# adalogger_featherwing.net
KiCad netlist of a schematic drawn in EAGLE
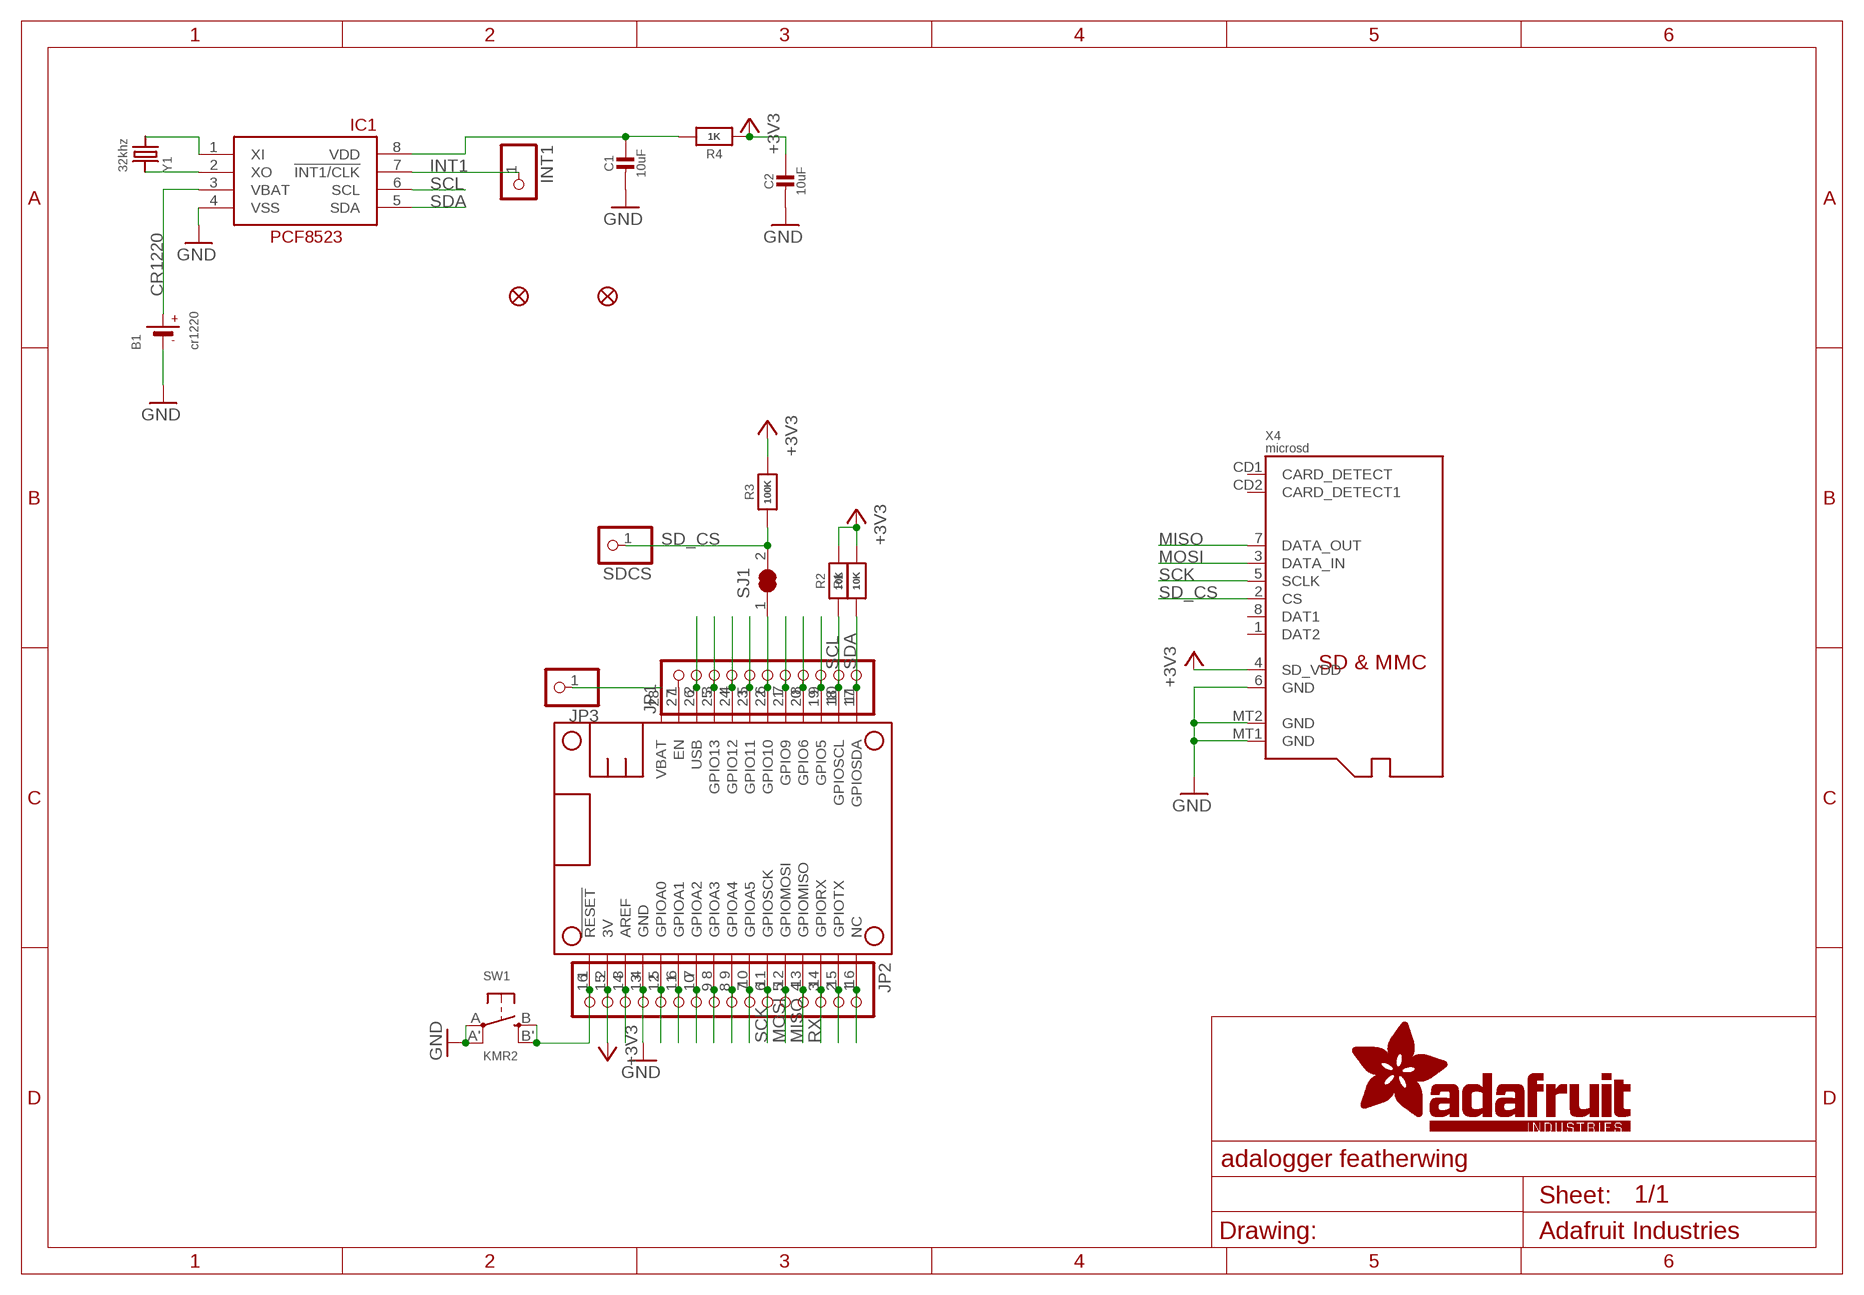
[diagram p0: schematic, sheet 1]

(export (version "E")
  (design (tool "Eeschema 10.0.6"))
  (components
    (comp (ref "B1")
      (value "cr1220")
      (footprint "eagle-import:CR1220-2")
      (libsource (lib "eagle-import") (part "BATTERYCR1220_2"))
    )
    (comp (ref "C1")
      (value "10uF")
      (footprint "eagle-import:0805-NO")
      (libsource (lib "eagle-import") (part "CAP_CERAMIC0805-NOOUTLINE"))
    )
    (comp (ref "C2")
      (value "10uF")
      (footprint "eagle-import:0805-NO")
      (libsource (lib "eagle-import") (part "CAP_CERAMIC0805-NOOUTLINE"))
    )
    (comp (ref "FID1")
      (value "FIDUCIAL_1MM")
      (footprint "eagle-import:FIDUCIAL_1MM")
      (libsource (lib "eagle-import") (part "FIDUCIAL_1MM"))
    )
    (comp (ref "FID2")
      (value "FIDUCIAL_1MM")
      (footprint "eagle-import:FIDUCIAL_1MM")
      (libsource (lib "eagle-import") (part "FIDUCIAL_1MM"))
    )
    (comp (ref "IC1")
      (value "PCF8523T")
      (footprint "eagle-import:SOIC8_150MIL")
      (libsource (lib "eagle-import") (part "RTC_PCF8523T"))
    )
    (comp (ref "INT1")
      (value "HEADER-1X1ROUND")
      (footprint "eagle-import:1X01_ROUND")
      (libsource (lib "eagle-import") (part "HEADER-1X1ROUND"))
    )
    (comp (ref "JP1")
      (value "HEADER-1X11")
      (footprint "eagle-import:1X11_ROUND")
      (libsource (lib "eagle-import") (part "HEADER-1X11"))
    )
    (comp (ref "JP2")
      (value "HEADER-1X16ROUND")
      (footprint "eagle-import:1X16_ROUND")
      (libsource (lib "eagle-import") (part "HEADER-1X16ROUND"))
    )
    (comp (ref "JP3")
      (value "HEADER-1X1ROUND")
      (footprint "eagle-import:1X01_ROUND")
      (libsource (lib "eagle-import") (part "HEADER-1X1ROUND"))
    )
    (comp (ref "MS1")
      (value "FEATHERWING_NODIM")
      (footprint "eagle-import:FEATHERWING_NODIM")
      (libsource (lib "eagle-import") (part "FEATHERWING_NODIM"))
    )
    (comp (ref "R1")
      (value "10K")
      (footprint "eagle-import:0603-NO")
      (libsource (lib "eagle-import") (part "RESISTOR_0603_NOOUT"))
    )
    (comp (ref "R2")
      (value "10K")
      (footprint "eagle-import:0603-NO")
      (libsource (lib "eagle-import") (part "RESISTOR_0603_NOOUT"))
    )
    (comp (ref "R3")
      (value "100K")
      (footprint "eagle-import:0603-NO")
      (libsource (lib "eagle-import") (part "RESISTOR_0603_NOOUT"))
    )
    (comp (ref "R4")
      (value "1K")
      (footprint "eagle-import:0603-NO")
      (libsource (lib "eagle-import") (part "RESISTOR_0603_NOOUT"))
    )
    (comp (ref "SDCS")
      (value "HEADER-1X1ROUND")
      (footprint "eagle-import:1X01_ROUND")
      (libsource (lib "eagle-import") (part "HEADER-1X1ROUND"))
    )
    (comp (ref "SJ1")
      (value "SOLDERJUMPER_CLOSED")
      (footprint "eagle-import:SOLDERJUMPER_CLOSEDWIRE")
      (libsource (lib "eagle-import") (part "SOLDERJUMPER_CLOSED"))
    )
    (comp (ref "SW1")
      (value "KMR2")
      (footprint "eagle-import:BTN_KMR2_4.6X2.8")
      (libsource (lib "eagle-import") (part "SWITCH_TACT_SMT4.6X2.8"))
    )
    (comp (ref "X4")
      (value "microsd")
      (footprint "eagle-import:MICROSD")
      (libsource (lib "eagle-import") (part "MICROSD"))
    )
    (comp (ref "Y1")
      (value "32khz")
      (footprint "eagle-import:CRYSTAL_8X3.8")
      (libsource (lib "eagle-import") (part "CRYSTAL8.0X3.8"))
    )
  )
  (nets
    (net (code "1") (name "+3V3") (class "Default")
      (node (ref "C2") (pin "1") (pinfunction "1_1") (pintype "passive"))
      (node (ref "JP2") (pin "15") (pinfunction "15_15") (pintype "passive"))
      (node (ref "MS1") (pin "2") (pinfunction "3V_2") (pintype "power_in"))
      (node (ref "R1") (pin "2") (pinfunction "2_2") (pintype "passive"))
      (node (ref "R2") (pin "2") (pinfunction "2_2") (pintype "passive"))
      (node (ref "R3") (pin "2") (pinfunction "2_2") (pintype "passive"))
      (node (ref "R4") (pin "1") (pinfunction "1_1") (pintype "passive"))
      (node (ref "X4") (pin "4") (pinfunction "SD_VDD_4") (pintype "power_in"))
    )
    (net (code "2") (name "/CR1220") (class "Default")
      (node (ref "B1") (pin "+") (pinfunction "+_+") (pintype "passive"))
      (node (ref "IC1") (pin "3") (pinfunction "VBAT_3") (pintype "power_in"))
    )
    (net (code "3") (name "/INT1") (class "Default")
      (node (ref "IC1") (pin "7") (pinfunction "~{INT1/CLK}_7") (pintype "output"))
      (node (ref "INT1") (pin "1") (pinfunction "1_1") (pintype "passive"))
    )
    (net (code "4") (name "/MISO") (class "Default")
      (node (ref "JP2") (pin "4") (pinfunction "4_4") (pintype "passive"))
      (node (ref "MS1") (pin "13") (pinfunction "GPIOMISO_13") (pintype "bidirectional"))
      (node (ref "X4") (pin "7") (pinfunction "DATA_OUT_7") (pintype "output"))
    )
    (net (code "5") (name "/MOSI") (class "Default")
      (node (ref "JP2") (pin "5") (pinfunction "5_5") (pintype "passive"))
      (node (ref "MS1") (pin "12") (pinfunction "GPIOMOSI_12") (pintype "bidirectional"))
      (node (ref "X4") (pin "3") (pinfunction "DATA_IN_3") (pintype "input"))
    )
    (net (code "6") (name "/RX") (class "Default")
      (node (ref "JP2") (pin "3") (pinfunction "3_3") (pintype "passive"))
      (node (ref "MS1") (pin "14") (pinfunction "GPIORX_14") (pintype "bidirectional"))
    )
    (net (code "7") (name "/SCK") (class "Default")
      (node (ref "JP2") (pin "6") (pinfunction "6_6") (pintype "passive"))
      (node (ref "MS1") (pin "11") (pinfunction "GPIOSCK_11") (pintype "bidirectional"))
      (node (ref "X4") (pin "5") (pinfunction "SCLK_5") (pintype "input"))
    )
    (net (code "8") (name "/SCL") (class "Default")
      (node (ref "IC1") (pin "6") (pinfunction "SCL_6") (pintype "bidirectional"))
      (node (ref "JP1") (pin "10") (pinfunction "10_10") (pintype "passive"))
      (node (ref "MS1") (pin "18") (pinfunction "GPIOSCL_18") (pintype "bidirectional"))
      (node (ref "R2") (pin "1") (pinfunction "1_1") (pintype "passive"))
    )
    (net (code "9") (name "/SDA") (class "Default")
      (node (ref "IC1") (pin "5") (pinfunction "SDA_5") (pintype "bidirectional"))
      (node (ref "JP1") (pin "11") (pinfunction "11_11") (pintype "passive"))
      (node (ref "MS1") (pin "17") (pinfunction "GPIOSDA_17") (pintype "bidirectional"))
      (node (ref "R1") (pin "1") (pinfunction "1_1") (pintype "passive"))
    )
    (net (code "10") (name "/SD_CS") (class "Default")
      (node (ref "R3") (pin "1") (pinfunction "1_1") (pintype "passive"))
      (node (ref "SDCS") (pin "1") (pinfunction "1_1") (pintype "passive"))
      (node (ref "SJ1") (pin "2") (pinfunction "2_2") (pintype "passive"))
      (node (ref "X4") (pin "2") (pinfunction "CS_2") (pintype "input"))
    )
    (net (code "11") (name "GND") (class "Default")
      (node (ref "B1") (pin "-") (pinfunction "-_-") (pintype "passive"))
      (node (ref "C1") (pin "2") (pinfunction "2_2") (pintype "passive"))
      (node (ref "C2") (pin "2") (pinfunction "2_2") (pintype "passive"))
      (node (ref "IC1") (pin "4") (pinfunction "VSS_4") (pintype "power_in"))
      (node (ref "JP2") (pin "13") (pinfunction "13_13") (pintype "passive"))
      (node (ref "MS1") (pin "4") (pinfunction "GND_4") (pintype "power_in"))
      (node (ref "SW1") (pin "A") (pinfunction "P_A") (pintype "passive"))
      (node (ref "SW1") (pin "A'") (pinfunction "P1_A'") (pintype "passive"))
      (node (ref "X4") (pin "6") (pinfunction "GND_6") (pintype "power_in"))
      (node (ref "X4") (pin "MT1") (pinfunction "GND_MT1") (pintype "power_in"))
      (node (ref "X4") (pin "MT2") (pinfunction "GND_MT2") (pintype "power_in"))
    )
    (net (code "12") (name "Net-(IC1-VDD)") (class "Default")
      (node (ref "C1") (pin "1") (pinfunction "1_1") (pintype "passive"))
      (node (ref "IC1") (pin "8") (pinfunction "VDD_8") (pintype "power_in"))
      (node (ref "R4") (pin "2") (pinfunction "2_2") (pintype "passive"))
    )
    (net (code "13") (name "Net-(IC1-XI)") (class "Default")
      (node (ref "IC1") (pin "1") (pinfunction "XI_1") (pintype "input"))
      (node (ref "Y1") (pin "P$4") (pinfunction "2_P$4") (pintype "passive"))
    )
    (net (code "14") (name "Net-(IC1-XO)") (class "Default")
      (node (ref "IC1") (pin "2") (pinfunction "XO_2") (pintype "output"))
      (node (ref "Y1") (pin "P$1") (pinfunction "1_P$1") (pintype "passive"))
    )
    (net (code "15") (name "Net-(MS1-AREF)") (class "Default")
      (node (ref "JP2") (pin "14") (pinfunction "14_14") (pintype "passive"))
      (node (ref "MS1") (pin "3") (pinfunction "AREF_3") (pintype "passive"))
    )
    (net (code "16") (name "Net-(MS1-EN)") (class "Default")
      (node (ref "JP1") (pin "1") (pinfunction "1_1") (pintype "passive"))
      (node (ref "MS1") (pin "27") (pinfunction "EN_27") (pintype "passive"))
    )
    (net (code "17") (name "Net-(MS1-GPIO5)") (class "Default")
      (node (ref "JP1") (pin "9") (pinfunction "9_9") (pintype "passive"))
      (node (ref "MS1") (pin "19") (pinfunction "GPIO5_19") (pintype "bidirectional"))
    )
    (net (code "18") (name "Net-(MS1-GPIO6)") (class "Default")
      (node (ref "JP1") (pin "8") (pinfunction "8_8") (pintype "passive"))
      (node (ref "MS1") (pin "20") (pinfunction "GPIO6_20") (pintype "bidirectional"))
    )
    (net (code "19") (name "Net-(MS1-GPIO9)") (class "Default")
      (node (ref "JP1") (pin "7") (pinfunction "7_7") (pintype "passive"))
      (node (ref "MS1") (pin "21") (pinfunction "GPIO9_21") (pintype "bidirectional"))
    )
    (net (code "20") (name "Net-(MS1-GPIO10)") (class "Default")
      (node (ref "JP1") (pin "6") (pinfunction "6_6") (pintype "passive"))
      (node (ref "MS1") (pin "22") (pinfunction "GPIO10_22") (pintype "bidirectional"))
      (node (ref "SJ1") (pin "1") (pinfunction "1_1") (pintype "passive"))
    )
    (net (code "21") (name "Net-(MS1-GPIO11)") (class "Default")
      (node (ref "JP1") (pin "5") (pinfunction "5_5") (pintype "passive"))
      (node (ref "MS1") (pin "23") (pinfunction "GPIO11_23") (pintype "bidirectional"))
    )
    (net (code "22") (name "Net-(MS1-GPIO12)") (class "Default")
      (node (ref "JP1") (pin "4") (pinfunction "4_4") (pintype "passive"))
      (node (ref "MS1") (pin "24") (pinfunction "GPIO12_24") (pintype "bidirectional"))
    )
    (net (code "23") (name "Net-(MS1-GPIO13)") (class "Default")
      (node (ref "JP1") (pin "3") (pinfunction "3_3") (pintype "passive"))
      (node (ref "MS1") (pin "25") (pinfunction "GPIO13_25") (pintype "bidirectional"))
    )
    (net (code "24") (name "Net-(MS1-GPIOA0)") (class "Default")
      (node (ref "JP2") (pin "12") (pinfunction "12_12") (pintype "passive"))
      (node (ref "MS1") (pin "5") (pinfunction "GPIOA0_5") (pintype "bidirectional"))
    )
    (net (code "25") (name "Net-(MS1-GPIOA1)") (class "Default")
      (node (ref "JP2") (pin "11") (pinfunction "11_11") (pintype "passive"))
      (node (ref "MS1") (pin "6") (pinfunction "GPIOA1_6") (pintype "bidirectional"))
    )
    (net (code "26") (name "Net-(MS1-GPIOA2)") (class "Default")
      (node (ref "JP2") (pin "10") (pinfunction "10_10") (pintype "passive"))
      (node (ref "MS1") (pin "7") (pinfunction "GPIOA2_7") (pintype "bidirectional"))
    )
    (net (code "27") (name "Net-(MS1-GPIOA3)") (class "Default")
      (node (ref "JP2") (pin "9") (pinfunction "9_9") (pintype "passive"))
      (node (ref "MS1") (pin "8") (pinfunction "GPIOA3_8") (pintype "bidirectional"))
    )
    (net (code "28") (name "Net-(MS1-GPIOA4)") (class "Default")
      (node (ref "JP2") (pin "8") (pinfunction "8_8") (pintype "passive"))
      (node (ref "MS1") (pin "9") (pinfunction "GPIOA4_9") (pintype "bidirectional"))
    )
    (net (code "29") (name "Net-(MS1-GPIOA5)") (class "Default")
      (node (ref "JP2") (pin "7") (pinfunction "7_7") (pintype "passive"))
      (node (ref "MS1") (pin "10") (pinfunction "GPIOA5_10") (pintype "bidirectional"))
    )
    (net (code "30") (name "Net-(MS1-GPIOTX)") (class "Default")
      (node (ref "JP2") (pin "2") (pinfunction "2_2") (pintype "passive"))
      (node (ref "MS1") (pin "15") (pinfunction "GPIOTX_15") (pintype "bidirectional"))
    )
    (net (code "31") (name "Net-(MS1-NC)") (class "Default")
      (node (ref "JP2") (pin "1") (pinfunction "1_1") (pintype "passive"))
      (node (ref "MS1") (pin "16") (pinfunction "NC_16") (pintype "passive"))
    )
    (net (code "32") (name "Net-(MS1-USB)") (class "Default")
      (node (ref "JP1") (pin "2") (pinfunction "2_2") (pintype "passive"))
      (node (ref "MS1") (pin "26") (pinfunction "USB_26") (pintype "power_in"))
    )
    (net (code "33") (name "Net-(MS1-VBAT)") (class "Default")
      (node (ref "JP3") (pin "1") (pinfunction "1_1") (pintype "passive"))
      (node (ref "MS1") (pin "28") (pinfunction "VBAT_28") (pintype "power_in"))
    )
    (net (code "34") (name "Net-(MS1-~{RESET})") (class "Default")
      (node (ref "JP2") (pin "16") (pinfunction "16_16") (pintype "passive"))
      (node (ref "MS1") (pin "1") (pinfunction "~{RESET}_1") (pintype "input"))
      (node (ref "SW1") (pin "B") (pinfunction "S_B") (pintype "passive"))
      (node (ref "SW1") (pin "B'") (pinfunction "S1_B'") (pintype "passive"))
    )
    (net (code "35") (name "unconnected-(X4-CARD_DETECT-PadCD1)") (class "Default")
      (node (ref "X4") (pin "CD1") (pinfunction "CARD_DETECT_CD1") (pintype "passive"))
    )
    (net (code "36") (name "unconnected-(X4-CARD_DETECT1-PadCD2)") (class "Default")
      (node (ref "X4") (pin "CD2") (pinfunction "CARD_DETECT1_CD2") (pintype "passive"))
    )
    (net (code "37") (name "unconnected-(X4-DAT1-Pad8)") (class "Default")
      (node (ref "X4") (pin "8") (pinfunction "DAT1_8") (pintype "bidirectional"))
    )
    (net (code "38") (name "unconnected-(X4-DAT2-Pad1)") (class "Default")
      (node (ref "X4") (pin "1") (pinfunction "DAT2_1") (pintype "bidirectional"))
    )
  )
)
